# I-O_Expander.net
KiCad netlist of a schematic drawn in Altium Designer
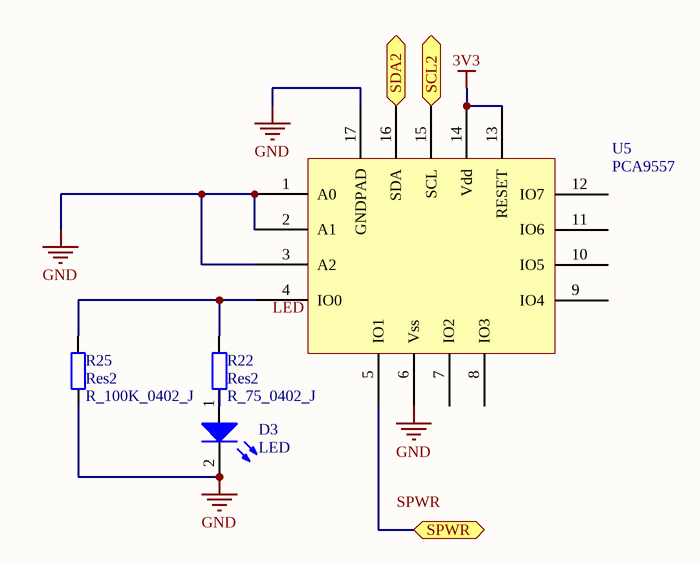
[diagram p0: I-O Expander.SchDoc]

(export (version "E")
  (design (tool "Eeschema 10.0.6"))
  (components
    (comp (ref "D3")
      (value "LED")
      (footprint "LED")
      (description "Typical RED GaAs LED")
      (fields (field (name "PUBLISHER") "Altium Limited"))
      (libsource (lib "Miscellaneous Devices") (part "LED1"))
    )
    (comp (ref "R22")
      (value "Res2")
      (footprint "R_0402")
      (description "Resistor")
      (fields (field (name "ALTIUM_VALUE") "R_75_0402_J") (field (name "PUBLISHER") "Altium Limited"))
      (libsource (lib "Miscellaneous Devices") (part "Res2"))
    )
    (comp (ref "R25")
      (value "Res2")
      (footprint "R_0402")
      (description "Resistor")
      (fields (field (name "ALTIUM_VALUE") "R_100K_0402_J"))
      (libsource (lib "Miscellaneous Devices") (part "Res2"))
    )
    (comp (ref "U5")
      (value "PCA9557")
      (footprint "PCA9557BS")
      (description "8 channel IO expander")
      (libsource (lib "BrewBit") (part "PCA9557"))
    )
  )
  (nets
    (net (code "2") (name "/SCL2") (class "Default")
      (node (ref "U5") (pin "15") (pinfunction "SCL_15") (pintype "passive"))
    )
    (net (code "3") (name "/SDA2") (class "Default")
      (node (ref "U5") (pin "16") (pinfunction "SDA_16") (pintype "passive"))
    )
    (net (code "4") (name "/SPWR") (class "Default")
      (node (ref "U5") (pin "5") (pinfunction "IO1_5") (pintype "passive"))
    )
    (net (code "5") (name "3V3") (class "Default")
      (node (ref "U5") (pin "13") (pinfunction "RESET_13") (pintype "passive"))
      (node (ref "U5") (pin "14") (pinfunction "Vdd_14") (pintype "passive"))
    )
    (net (code "6") (name "GND") (class "Default")
      (node (ref "D3") (pin "2") (pinfunction "K_2") (pintype "passive"))
      (node (ref "R25") (pin "1") (pinfunction "1_1") (pintype "passive"))
      (node (ref "U5") (pin "1") (pinfunction "A0_1") (pintype "passive"))
      (node (ref "U5") (pin "17") (pinfunction "GNDPAD_17") (pintype "passive"))
      (node (ref "U5") (pin "2") (pinfunction "A1_2") (pintype "passive"))
      (node (ref "U5") (pin "3") (pinfunction "A2_3") (pintype "passive"))
      (node (ref "U5") (pin "6") (pinfunction "Vss_6") (pintype "passive"))
    )
    (net (code "7") (name "Net-(D3-A)") (class "Default")
      (node (ref "D3") (pin "1") (pinfunction "A_1") (pintype "passive"))
      (node (ref "R22") (pin "1") (pinfunction "1_1") (pintype "passive"))
    )
    (net (code "8") (name "Net-(U5-IO0)") (class "Default")
      (node (ref "R22") (pin "2") (pinfunction "2_2") (pintype "passive"))
      (node (ref "R25") (pin "2") (pinfunction "2_2") (pintype "passive"))
      (node (ref "U5") (pin "4") (pinfunction "IO0_4") (pintype "passive"))
    )
    (net (code "9") (name "unconnected-(U5-IO2-Pad7)") (class "Default")
      (node (ref "U5") (pin "7") (pinfunction "IO2_7") (pintype "passive"))
    )
    (net (code "10") (name "unconnected-(U5-IO3-Pad8)") (class "Default")
      (node (ref "U5") (pin "8") (pinfunction "IO3_8") (pintype "passive"))
    )
    (net (code "11") (name "unconnected-(U5-IO4-Pad9)") (class "Default")
      (node (ref "U5") (pin "9") (pinfunction "IO4_9") (pintype "passive"))
    )
    (net (code "12") (name "unconnected-(U5-IO5-Pad10)") (class "Default")
      (node (ref "U5") (pin "10") (pinfunction "IO5_10") (pintype "passive"))
    )
    (net (code "13") (name "unconnected-(U5-IO6-Pad11)") (class "Default")
      (node (ref "U5") (pin "11") (pinfunction "IO6_11") (pintype "passive"))
    )
    (net (code "14") (name "unconnected-(U5-IO7-Pad12)") (class "Default")
      (node (ref "U5") (pin "12") (pinfunction "IO7_12") (pintype "passive"))
    )
  )
)
